# 13_SPI_Flash.net
KiCad netlist of a schematic drawn in Altium Designer
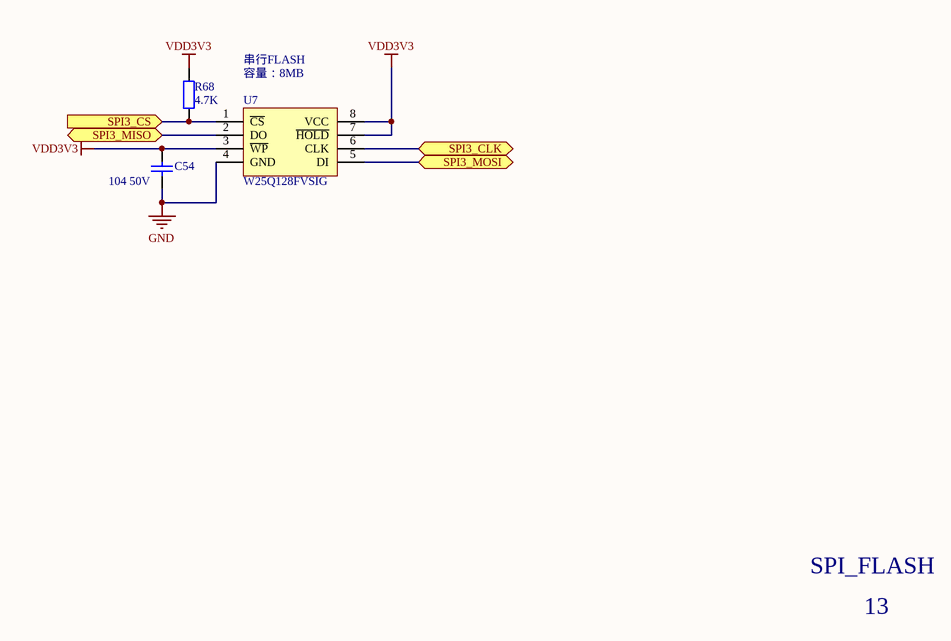
[diagram p0: 13_SPI_Flash.SchDoc]

(export (version "E")
  (design (tool "Eeschema 10.0.6"))
  (components
    (comp (ref "C54")
      (value "104 50V")
      (footprint "SMD-0603C")
      (description "贴片电容 20%")
      (libsource (lib "XiaoyI") (part "CAP4"))
    )
    (comp (ref "R68")
      (value "4.7K")
      (footprint "SMD-0603")
      (description "贴片电阻 5%")
      (libsource (lib "XiaoyI") (part "RES2"))
    )
    (comp (ref "U7")
      (value "W25Q128FVSIG")
      (footprint "SO-8W")
      (libsource (lib "YS-F1Pro开发板主板") (part "W25Q128FV"))
    )
  )
  (nets
    (net (code "1") (name "/SPI3_CLK") (class "Default")
      (node (ref "U7") (pin "6") (pinfunction "CLK_6") (pintype "passive"))
    )
    (net (code "2") (name "/SPI3_CS") (class "Default")
      (node (ref "R68") (pin "2") (pinfunction "2_2") (pintype "passive"))
      (node (ref "U7") (pin "1") (pinfunction "~{CS}_1") (pintype "passive"))
    )
    (net (code "3") (name "/SPI3_MISO") (class "Default")
      (node (ref "U7") (pin "2") (pinfunction "DO_2") (pintype "passive"))
    )
    (net (code "4") (name "/SPI3_MOSI") (class "Default")
      (node (ref "U7") (pin "5") (pinfunction "DI_5") (pintype "passive"))
    )
    (net (code "5") (name "GND") (class "Default")
      (node (ref "C54") (pin "2") (pinfunction "2_2") (pintype "passive"))
      (node (ref "U7") (pin "4") (pinfunction "GND_4") (pintype "passive"))
    )
    (net (code "6") (name "VDD3V3") (class "Default")
      (node (ref "C54") (pin "1") (pinfunction "1_1") (pintype "passive"))
      (node (ref "R68") (pin "1") (pinfunction "1_1") (pintype "passive"))
      (node (ref "U7") (pin "3") (pinfunction "~{WP}_3") (pintype "passive"))
      (node (ref "U7") (pin "7") (pinfunction "~{HOLD}_7") (pintype "passive"))
      (node (ref "U7") (pin "8") (pinfunction "VCC_8") (pintype "passive"))
    )
  )
)
